# MJ808_clone_-_all_driver_-_prod_-_23mm.net
KiCad netlist of a schematic drawn in EAGLE
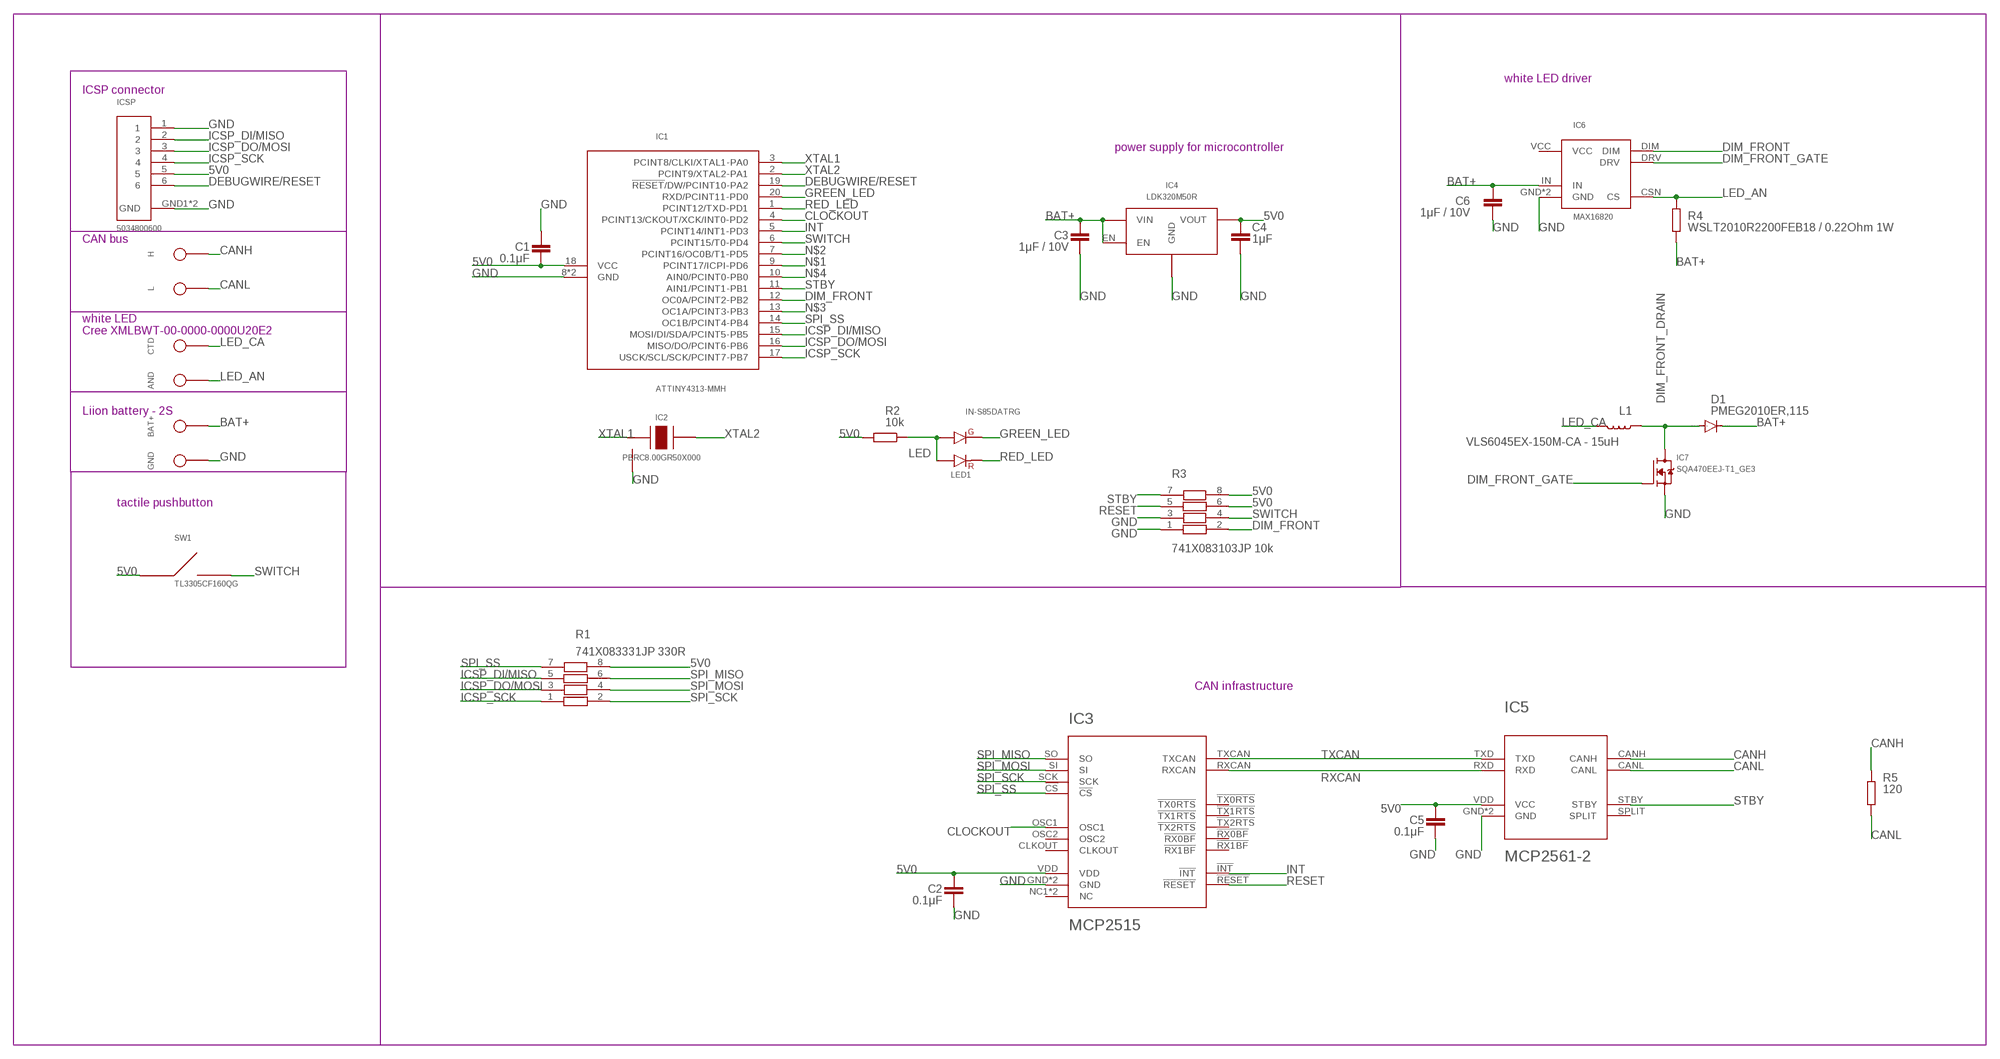
[diagram p0: schematic, sheet 1]

(export (version "E")
  (design (tool "Eeschema 10.0.6"))
  (components
    (comp (ref "AND")
      (value "LED anode")
      (footprint "eagle-import:TH-0.9MM")
      (libsource (lib "eagle-import") (part "TPTH-0.9MM"))
    )
    (comp (ref "BAT+")
      (value "LiIon + Terminal")
      (footprint "eagle-import:TH-0.9MM")
      (libsource (lib "eagle-import") (part "TPTH-0.9MM"))
    )
    (comp (ref "C1")
      (value "0.1μF")
      (footprint "eagle-import:C0402")
      (libsource (lib "eagle-import") (part "C-EUC0402"))
    )
    (comp (ref "C2")
      (value "0.1μF")
      (footprint "eagle-import:C0402")
      (libsource (lib "eagle-import") (part "C-EUC0402"))
    )
    (comp (ref "C3")
      (value "1μF / 10V")
      (footprint "eagle-import:C0402")
      (libsource (lib "eagle-import") (part "C-EUC0402"))
    )
    (comp (ref "C4")
      (value "1μF")
      (footprint "eagle-import:C0402")
      (libsource (lib "eagle-import") (part "C-EUC0402"))
    )
    (comp (ref "C5")
      (value "0.1μF")
      (footprint "eagle-import:C0402")
      (libsource (lib "eagle-import") (part "C-EUC0402"))
    )
    (comp (ref "C6")
      (value "1μF / 10V")
      (footprint "eagle-import:C0402")
      (libsource (lib "eagle-import") (part "C-EUC0402"))
    )
    (comp (ref "CTD")
      (value "LED cathode")
      (footprint "eagle-import:TH-0.9MM")
      (libsource (lib "eagle-import") (part "TPTH-0.9MM"))
    )
    (comp (ref "D1")
      (value "PMEG2010ER,115")
      (footprint "eagle-import:SOD123")
      (libsource (lib "eagle-import") (part "DIODE-SOD123"))
    )
    (comp (ref "GND")
      (value "LiIon - Terminal")
      (footprint "eagle-import:TH-0.9MM")
      (libsource (lib "eagle-import") (part "TPTH-0.9MM"))
    )
    (comp (ref "H")
      (value "CAN high")
      (footprint "eagle-import:SMT-1.2MM")
      (libsource (lib "eagle-import") (part "TPSMT-1.2MM"))
    )
    (comp (ref "IC1")
      (value "ATTINY4313-MMH")
      (footprint "eagle-import:VQFN-20")
      (fields (field (name "SPICEPREFIX") "X"))
      (libsource (lib "eagle-import") (part "ATTINY4313VQFN-20"))
    )
    (comp (ref "IC2")
      (value "PBRC8.00GR50X000")
      (footprint "eagle-import:SMT")
      (libsource (lib "eagle-import") (part "PRQV"))
    )
    (comp (ref "IC3")
      (value "MCP2515")
      (footprint "eagle-import:QFN20")
      (libsource (lib "eagle-import") (part "MCP2515-I-ML"))
    )
    (comp (ref "IC4")
      (value "LDK320M50R")
      (footprint "eagle-import:SOT-23-5L")
      (libsource (lib "eagle-import") (part "LDK320SOT-23-5L"))
    )
    (comp (ref "IC5")
      (value "MCP2561-2")
      (footprint "eagle-import:DFN10")
      (libsource (lib "eagle-import") (part "MCP2561-2"))
    )
    (comp (ref "IC6")
      (value "MAX16820")
      (footprint "eagle-import:TDFN-6-EP")
      (libsource (lib "eagle-import") (part "MAX16820"))
    )
    (comp (ref "IC7")
      (value "SQA470EEJ-T1_GE3")
      (footprint "eagle-import:SC-70-6")
      (libsource (lib "eagle-import") (part "SIA456DJ"))
    )
    (comp (ref "ICSP")
      (value "5034800600")
      (footprint "eagle-import:SMT")
      (libsource (lib "eagle-import") (part "5034800600"))
    )
    (comp (ref "L")
      (value "CAN low")
      (footprint "eagle-import:SMT-1.2MM")
      (libsource (lib "eagle-import") (part "TPSMT-1.2MM"))
    )
    (comp (ref "L1")
      (value "VLS6045EX-150M-CA - 15uH")
      (footprint "eagle-import:SRN6045")
      (libsource (lib "eagle-import") (part "INDUCTOR-SRN6045-33UH"))
    )
    (comp (ref "LED1")
      (value "IN-S85DATRG")
      (footprint "eagle-import:SMD")
      (libsource (lib "eagle-import") (part "APHBM2012LSURKZGKC"))
    )
    (comp (ref "R1")
      (value "741X083331JP 330R")
      (footprint "eagle-import:0402-4R")
      (libsource (lib "eagle-import") (part "741X083331JP"))
    )
    (comp (ref "R2")
      (value "10k")
      (footprint "eagle-import:R0402")
      (libsource (lib "eagle-import") (part "R-EU_R0402"))
    )
    (comp (ref "R3")
      (value "741X083103JP 10k")
      (footprint "eagle-import:0402-4R")
      (libsource (lib "eagle-import") (part "741X083331JP"))
    )
    (comp (ref "R4")
      (value "WSLT2010R2200FEB18 / 0.22Ohm 1W")
      (footprint "eagle-import:R2010")
      (libsource (lib "eagle-import") (part "R-EU_R2010"))
    )
    (comp (ref "R5")
      (value "120")
      (footprint "eagle-import:R0805")
      (libsource (lib "eagle-import") (part "R-EU_R0805"))
    )
    (comp (ref "SW1")
      (value "TL3305CF160QG")
      (footprint "eagle-import:SMD")
      (libsource (lib "eagle-import") (part "TL3305-844809"))
    )
  )
  (nets
    (net (code "1") (name "/5V0") (class "Default")
      (node (ref "C1") (pin "1") (pinfunction "1_1") (pintype "passive"))
      (node (ref "C2") (pin "1") (pinfunction "1_1") (pintype "passive"))
      (node (ref "C4") (pin "2") (pinfunction "2_2") (pintype "passive"))
      (node (ref "C5") (pin "1") (pinfunction "1_1") (pintype "passive"))
      (node (ref "IC1") (pin "18") (pinfunction "VCC_18") (pintype "bidirectional"))
      (node (ref "IC3") (pin "VDD") (pinfunction "VDD_VDD") (pintype "power_in"))
      (node (ref "IC4") (pin "OUT") (pinfunction "VOUT_OUT") (pintype "bidirectional"))
      (node (ref "IC5") (pin "VDD") (pinfunction "VCC_VDD") (pintype "power_in"))
      (node (ref "ICSP") (pin "5") (pinfunction "5_5") (pintype "bidirectional"))
      (node (ref "R1") (pin "8") (pinfunction "8_8") (pintype "bidirectional"))
      (node (ref "R2") (pin "2") (pinfunction "2_2") (pintype "passive"))
      (node (ref "R3") (pin "6") (pinfunction "6_6") (pintype "bidirectional"))
      (node (ref "R3") (pin "8") (pinfunction "8_8") (pintype "bidirectional"))
      (node (ref "SW1") (pin "1") (pinfunction "P$1_1") (pintype "bidirectional"))
      (node (ref "SW1") (pin "2") (pinfunction "P$1_2") (pintype "bidirectional"))
    )
    (net (code "2") (name "/BAT+") (class "Default")
      (node (ref "BAT+") (pin "TP$1") (pinfunction "TP$1_TP$1") (pintype "bidirectional"))
      (node (ref "C3") (pin "1") (pinfunction "1_1") (pintype "passive"))
      (node (ref "C6") (pin "1") (pinfunction "1_1") (pintype "passive"))
      (node (ref "D1") (pin "C") (pinfunction "C_C") (pintype "passive"))
      (node (ref "IC4") (pin "EN") (pinfunction "EN_EN") (pintype "bidirectional"))
      (node (ref "IC4") (pin "IN") (pinfunction "VIN_IN") (pintype "bidirectional"))
      (node (ref "IC6") (pin "IN") (pinfunction "IN_IN") (pintype "power_in"))
      (node (ref "R4") (pin "2") (pinfunction "2_2") (pintype "passive"))
    )
    (net (code "3") (name "/CANH") (class "Default")
      (node (ref "H") (pin "P$1") (pinfunction "TP$1_P$1") (pintype "bidirectional"))
      (node (ref "IC5") (pin "CANH") (pinfunction "CANH_CANH") (pintype "bidirectional"))
      (node (ref "R5") (pin "2") (pinfunction "2_2") (pintype "passive"))
    )
    (net (code "4") (name "/CANL") (class "Default")
      (node (ref "IC5") (pin "CANL") (pinfunction "CANL_CANL") (pintype "bidirectional"))
      (node (ref "L") (pin "P$1") (pinfunction "TP$1_P$1") (pintype "bidirectional"))
      (node (ref "R5") (pin "1") (pinfunction "1_1") (pintype "passive"))
    )
    (net (code "5") (name "/CLOCKOUT") (class "Default")
      (node (ref "IC1") (pin "4") (pinfunction "PCINT13/CKOUT/XCK/INT0-PD2_4") (pintype "bidirectional"))
      (node (ref "IC3") (pin "OSC1") (pinfunction "OSC1_OSC1") (pintype "bidirectional"))
    )
    (net (code "6") (name "/DEBUGWIRE{slash}RESET") (class "Default")
      (node (ref "IC1") (pin "19") (pinfunction "~{RESET}/DW/PCINT10-PA2_19") (pintype "bidirectional"))
      (node (ref "ICSP") (pin "6") (pinfunction "6_6") (pintype "bidirectional"))
    )
    (net (code "7") (name "/DIM_FRONT") (class "Default")
      (node (ref "IC1") (pin "12") (pinfunction "OC0A/PCINT2-PB2_12") (pintype "bidirectional"))
      (node (ref "IC6") (pin "DIM") (pinfunction "DIM_DIM") (pintype "bidirectional"))
      (node (ref "R3") (pin "2") (pinfunction "2_2") (pintype "bidirectional"))
    )
    (net (code "8") (name "/DIM_FRONT_DRAIN") (class "Default")
      (node (ref "D1") (pin "A") (pinfunction "A_A") (pintype "passive"))
      (node (ref "IC7") (pin "1D") (pinfunction "D_1D") (pintype "passive"))
      (node (ref "IC7") (pin "2D") (pinfunction "D_2D") (pintype "passive"))
      (node (ref "IC7") (pin "5D") (pinfunction "D_5D") (pintype "passive"))
      (node (ref "IC7") (pin "6D") (pinfunction "D_6D") (pintype "passive"))
      (node (ref "IC7") (pin "D") (pinfunction "D_D") (pintype "passive"))
      (node (ref "L1") (pin "1") (pinfunction "1_1") (pintype "passive"))
    )
    (net (code "9") (name "/DIM_FRONT_GATE") (class "Default")
      (node (ref "IC6") (pin "DRV") (pinfunction "DRV_DRV") (pintype "bidirectional"))
      (node (ref "IC7") (pin "3G") (pinfunction "G_3G") (pintype "passive"))
    )
    (net (code "10") (name "/GND") (class "Default")
      (node (ref "C1") (pin "2") (pinfunction "2_2") (pintype "passive"))
      (node (ref "C2") (pin "2") (pinfunction "2_2") (pintype "passive"))
      (node (ref "C3") (pin "2") (pinfunction "2_2") (pintype "passive"))
      (node (ref "C4") (pin "1") (pinfunction "1_1") (pintype "passive"))
      (node (ref "C5") (pin "2") (pinfunction "2_2") (pintype "passive"))
      (node (ref "C6") (pin "2") (pinfunction "2_2") (pintype "passive"))
      (node (ref "GND") (pin "TP$1") (pinfunction "TP$1_TP$1") (pintype "bidirectional"))
      (node (ref "IC1") (pin "8") (pinfunction "GND_8") (pintype "bidirectional"))
      (node (ref "IC1") (pin "GND") (pinfunction "GND_GND") (pintype "bidirectional"))
      (node (ref "IC2") (pin "GND") (pinfunction "GND_GND") (pintype "bidirectional"))
      (node (ref "IC3") (pin "GND") (pinfunction "GND_GND") (pintype "power_in"))
      (node (ref "IC3") (pin "GND6") (pinfunction "GND_GND6") (pintype "power_in"))
      (node (ref "IC4") (pin "GND") (pinfunction "GND_GND") (pintype "bidirectional"))
      (node (ref "IC5") (pin "GND") (pinfunction "GND_GND") (pintype "power_in"))
      (node (ref "IC5") (pin "VSS") (pinfunction "GND_VSS") (pintype "power_in"))
      (node (ref "IC6") (pin "GND") (pinfunction "GND_GND") (pintype "power_in"))
      (node (ref "IC6") (pin "GND1") (pinfunction "GND_GND1") (pintype "power_in"))
      (node (ref "IC7") (pin "4S") (pinfunction "S_4S") (pintype "passive"))
      (node (ref "IC7") (pin "S") (pinfunction "S_S") (pintype "passive"))
      (node (ref "ICSP") (pin "1") (pinfunction "1_1") (pintype "bidirectional"))
      (node (ref "ICSP") (pin "GND1") (pinfunction "GND_GND1") (pintype "bidirectional"))
      (node (ref "ICSP") (pin "GND2") (pinfunction "GND_GND2") (pintype "bidirectional"))
      (node (ref "R3") (pin "1") (pinfunction "1_1") (pintype "bidirectional"))
      (node (ref "R3") (pin "3") (pinfunction "3_3") (pintype "bidirectional"))
    )
    (net (code "11") (name "/GREEN_LED") (class "Default")
      (node (ref "IC1") (pin "20") (pinfunction "RXD/PCINT11-PD0_20") (pintype "bidirectional"))
      (node (ref "LED1") (pin "3") (pinfunction "3_3") (pintype "bidirectional"))
    )
    (net (code "12") (name "/ICSP_DI{slash}MISO") (class "Default")
      (node (ref "IC1") (pin "15") (pinfunction "MOSI/DI/SDA/PCINT5-PB5_15") (pintype "bidirectional"))
      (node (ref "ICSP") (pin "2") (pinfunction "2_2") (pintype "bidirectional"))
      (node (ref "R1") (pin "5") (pinfunction "5_5") (pintype "bidirectional"))
    )
    (net (code "13") (name "/ICSP_DO{slash}MOSI") (class "Default")
      (node (ref "IC1") (pin "16") (pinfunction "MISO/DO/PCINT6-PB6_16") (pintype "bidirectional"))
      (node (ref "ICSP") (pin "3") (pinfunction "3_3") (pintype "bidirectional"))
      (node (ref "R1") (pin "3") (pinfunction "3_3") (pintype "bidirectional"))
    )
    (net (code "14") (name "/ICSP_SCK") (class "Default")
      (node (ref "IC1") (pin "17") (pinfunction "USCK/SCL/SCK/PCINT7-PB7_17") (pintype "bidirectional"))
      (node (ref "ICSP") (pin "4") (pinfunction "4_4") (pintype "bidirectional"))
      (node (ref "R1") (pin "1") (pinfunction "1_1") (pintype "bidirectional"))
    )
    (net (code "15") (name "/INT") (class "Default")
      (node (ref "IC1") (pin "5") (pinfunction "PCINT14/INT1-PD3_5") (pintype "bidirectional"))
      (node (ref "IC3") (pin "!INT!") (pinfunction "~{INT}_!INT!") (pintype "bidirectional"))
    )
    (net (code "16") (name "/LED") (class "Default")
      (node (ref "LED1") (pin "1") (pinfunction "1_1") (pintype "bidirectional"))
      (node (ref "LED1") (pin "4") (pinfunction "4_4") (pintype "bidirectional"))
      (node (ref "R2") (pin "1") (pinfunction "1_1") (pintype "passive"))
    )
    (net (code "17") (name "/LED_AN") (class "Default")
      (node (ref "AND") (pin "TP$1") (pinfunction "TP$1_TP$1") (pintype "bidirectional"))
      (node (ref "IC6") (pin "CSN") (pinfunction "CS_CSN") (pintype "bidirectional"))
      (node (ref "R4") (pin "1") (pinfunction "1_1") (pintype "passive"))
    )
    (net (code "18") (name "/LED_CA") (class "Default")
      (node (ref "CTD") (pin "TP$1") (pinfunction "TP$1_TP$1") (pintype "bidirectional"))
      (node (ref "L1") (pin "2") (pinfunction "2_2") (pintype "passive"))
    )
    (net (code "19") (name "/N$1") (class "Default")
      (node (ref "IC1") (pin "9") (pinfunction "PCINT17/ICPI-PD6_9") (pintype "bidirectional"))
    )
    (net (code "20") (name "/N$2") (class "Default")
      (node (ref "IC1") (pin "7") (pinfunction "PCINT16/OC0B/T1-PD5_7") (pintype "bidirectional"))
    )
    (net (code "21") (name "/N$3") (class "Default")
      (node (ref "IC1") (pin "13") (pinfunction "OC1A/PCINT3-PB3_13") (pintype "bidirectional"))
    )
    (net (code "22") (name "/N$4") (class "Default")
      (node (ref "IC1") (pin "10") (pinfunction "AIN0/PCINT0-PB0_10") (pintype "bidirectional"))
    )
    (net (code "23") (name "/RED_LED") (class "Default")
      (node (ref "IC1") (pin "1") (pinfunction "PCINT12/TXD-PD1_1") (pintype "bidirectional"))
      (node (ref "LED1") (pin "2") (pinfunction "2_2") (pintype "bidirectional"))
    )
    (net (code "24") (name "/RESET") (class "Default")
      (node (ref "IC3") (pin "!RESET!") (pinfunction "~{RESET}_!RESET!") (pintype "bidirectional"))
      (node (ref "R3") (pin "5") (pinfunction "5_5") (pintype "bidirectional"))
    )
    (net (code "25") (name "/RXCAN") (class "Default")
      (node (ref "IC3") (pin "RXCAN") (pinfunction "RXCAN_RXCAN") (pintype "input"))
      (node (ref "IC5") (pin "RXD") (pinfunction "RXD_RXD") (pintype "output"))
    )
    (net (code "26") (name "/SPI_MISO") (class "Default")
      (node (ref "IC3") (pin "SO") (pinfunction "SO_SO") (pintype "output"))
      (node (ref "R1") (pin "6") (pinfunction "6_6") (pintype "bidirectional"))
    )
    (net (code "27") (name "/SPI_MOSI") (class "Default")
      (node (ref "IC3") (pin "SI") (pinfunction "SI_SI") (pintype "input"))
      (node (ref "R1") (pin "4") (pinfunction "4_4") (pintype "bidirectional"))
    )
    (net (code "28") (name "/SPI_SCK") (class "Default")
      (node (ref "IC3") (pin "SCK") (pinfunction "SCK_SCK") (pintype "bidirectional"))
      (node (ref "R1") (pin "2") (pinfunction "2_2") (pintype "bidirectional"))
    )
    (net (code "29") (name "/SPI_SS") (class "Default")
      (node (ref "IC1") (pin "14") (pinfunction "OC1B/PCINT4-PB4_14") (pintype "bidirectional"))
      (node (ref "IC3") (pin "!CS!") (pinfunction "~{CS}_!CS!") (pintype "bidirectional"))
      (node (ref "R1") (pin "7") (pinfunction "7_7") (pintype "bidirectional"))
    )
    (net (code "30") (name "/STBY") (class "Default")
      (node (ref "IC1") (pin "11") (pinfunction "AIN1/PCINT1-PB1_11") (pintype "bidirectional"))
      (node (ref "IC5") (pin "STBY") (pinfunction "STBY_STBY") (pintype "bidirectional"))
      (node (ref "R3") (pin "7") (pinfunction "7_7") (pintype "bidirectional"))
    )
    (net (code "31") (name "/SWITCH") (class "Default")
      (node (ref "IC1") (pin "6") (pinfunction "PCINT15/T0-PD4_6") (pintype "bidirectional"))
      (node (ref "R3") (pin "4") (pinfunction "4_4") (pintype "bidirectional"))
      (node (ref "SW1") (pin "3") (pinfunction "P$2_3") (pintype "bidirectional"))
      (node (ref "SW1") (pin "4") (pinfunction "P$2_4") (pintype "bidirectional"))
    )
    (net (code "32") (name "/TXCAN") (class "Default")
      (node (ref "IC3") (pin "TXCAN") (pinfunction "TXCAN_TXCAN") (pintype "output"))
      (node (ref "IC5") (pin "TXD") (pinfunction "TXD_TXD") (pintype "input"))
    )
    (net (code "33") (name "/VCC") (class "Default")
      (node (ref "IC6") (pin "VCC") (pinfunction "VCC_VCC") (pintype "power_in"))
    )
    (net (code "34") (name "/XTAL1") (class "Default")
      (node (ref "IC1") (pin "3") (pinfunction "PCINT8/CLKI/XTAL1-PA0_3") (pintype "bidirectional"))
      (node (ref "IC2") (pin "XTAL1") (pinfunction "XTAL1_XTAL1") (pintype "bidirectional"))
    )
    (net (code "35") (name "/XTAL2") (class "Default")
      (node (ref "IC1") (pin "2") (pinfunction "PCINT9/XTAL2-PA1_2") (pintype "bidirectional"))
      (node (ref "IC2") (pin "XTAL2") (pinfunction "XTAL2_XTAL2") (pintype "bidirectional"))
    )
    (net (code "36") (name "unconnected-(IC3-NC-PadNC1)") (class "Default")
      (node (ref "IC3") (pin "NC1") (pinfunction "NC_NC1") (pintype "no_connect"))
    )
    (net (code "37") (name "unconnected-(IC3-NC-PadNC2)") (class "Default")
      (node (ref "IC3") (pin "NC2") (pinfunction "NC_NC2") (pintype "no_connect"))
    )
    (net (code "38") (name "unconnected-(IC3-PadCLKOUT)") (class "Default")
      (node (ref "IC3") (pin "CLKOUT") (pinfunction "CLKOUT_CLKOUT") (pintype "bidirectional"))
    )
    (net (code "39") (name "unconnected-(IC3-PadOSC2)") (class "Default")
      (node (ref "IC3") (pin "OSC2") (pinfunction "OSC2_OSC2") (pintype "bidirectional"))
    )
    (net (code "40") (name "unconnected-(IC3-~{RX0BF}-Pad!RX0BF!)") (class "Default")
      (node (ref "IC3") (pin "!RX0BF!") (pinfunction "~{RX0BF}_!RX0BF!") (pintype "bidirectional"))
    )
    (net (code "41") (name "unconnected-(IC3-~{RX1BF}-Pad!RX1BF!)") (class "Default")
      (node (ref "IC3") (pin "!RX1BF!") (pinfunction "~{RX1BF}_!RX1BF!") (pintype "bidirectional"))
    )
    (net (code "42") (name "unconnected-(IC3-~{TX0RTS}-Pad!TX0RTS!)") (class "Default")
      (node (ref "IC3") (pin "!TX0RTS!") (pinfunction "~{TX0RTS}_!TX0RTS!") (pintype "bidirectional"))
    )
    (net (code "43") (name "unconnected-(IC3-~{TX1RTS}-Pad!TX1RTS!)") (class "Default")
      (node (ref "IC3") (pin "!TX1RTS!") (pinfunction "~{TX1RTS}_!TX1RTS!") (pintype "bidirectional"))
    )
    (net (code "44") (name "unconnected-(IC3-~{TX2RTS}-Pad!TX2RTS!)") (class "Default")
      (node (ref "IC3") (pin "!TX2RTS!") (pinfunction "~{TX2RTS}_!TX2RTS!") (pintype "bidirectional"))
    )
    (net (code "45") (name "unconnected-(IC5-PadSPLIT)") (class "Default")
      (node (ref "IC5") (pin "SPLIT") (pinfunction "SPLIT_SPLIT") (pintype "bidirectional"))
    )
  )
)
